# MC21R01_Onboard_temp_sensors.net
KiCad netlist of a schematic drawn in Altium Designer
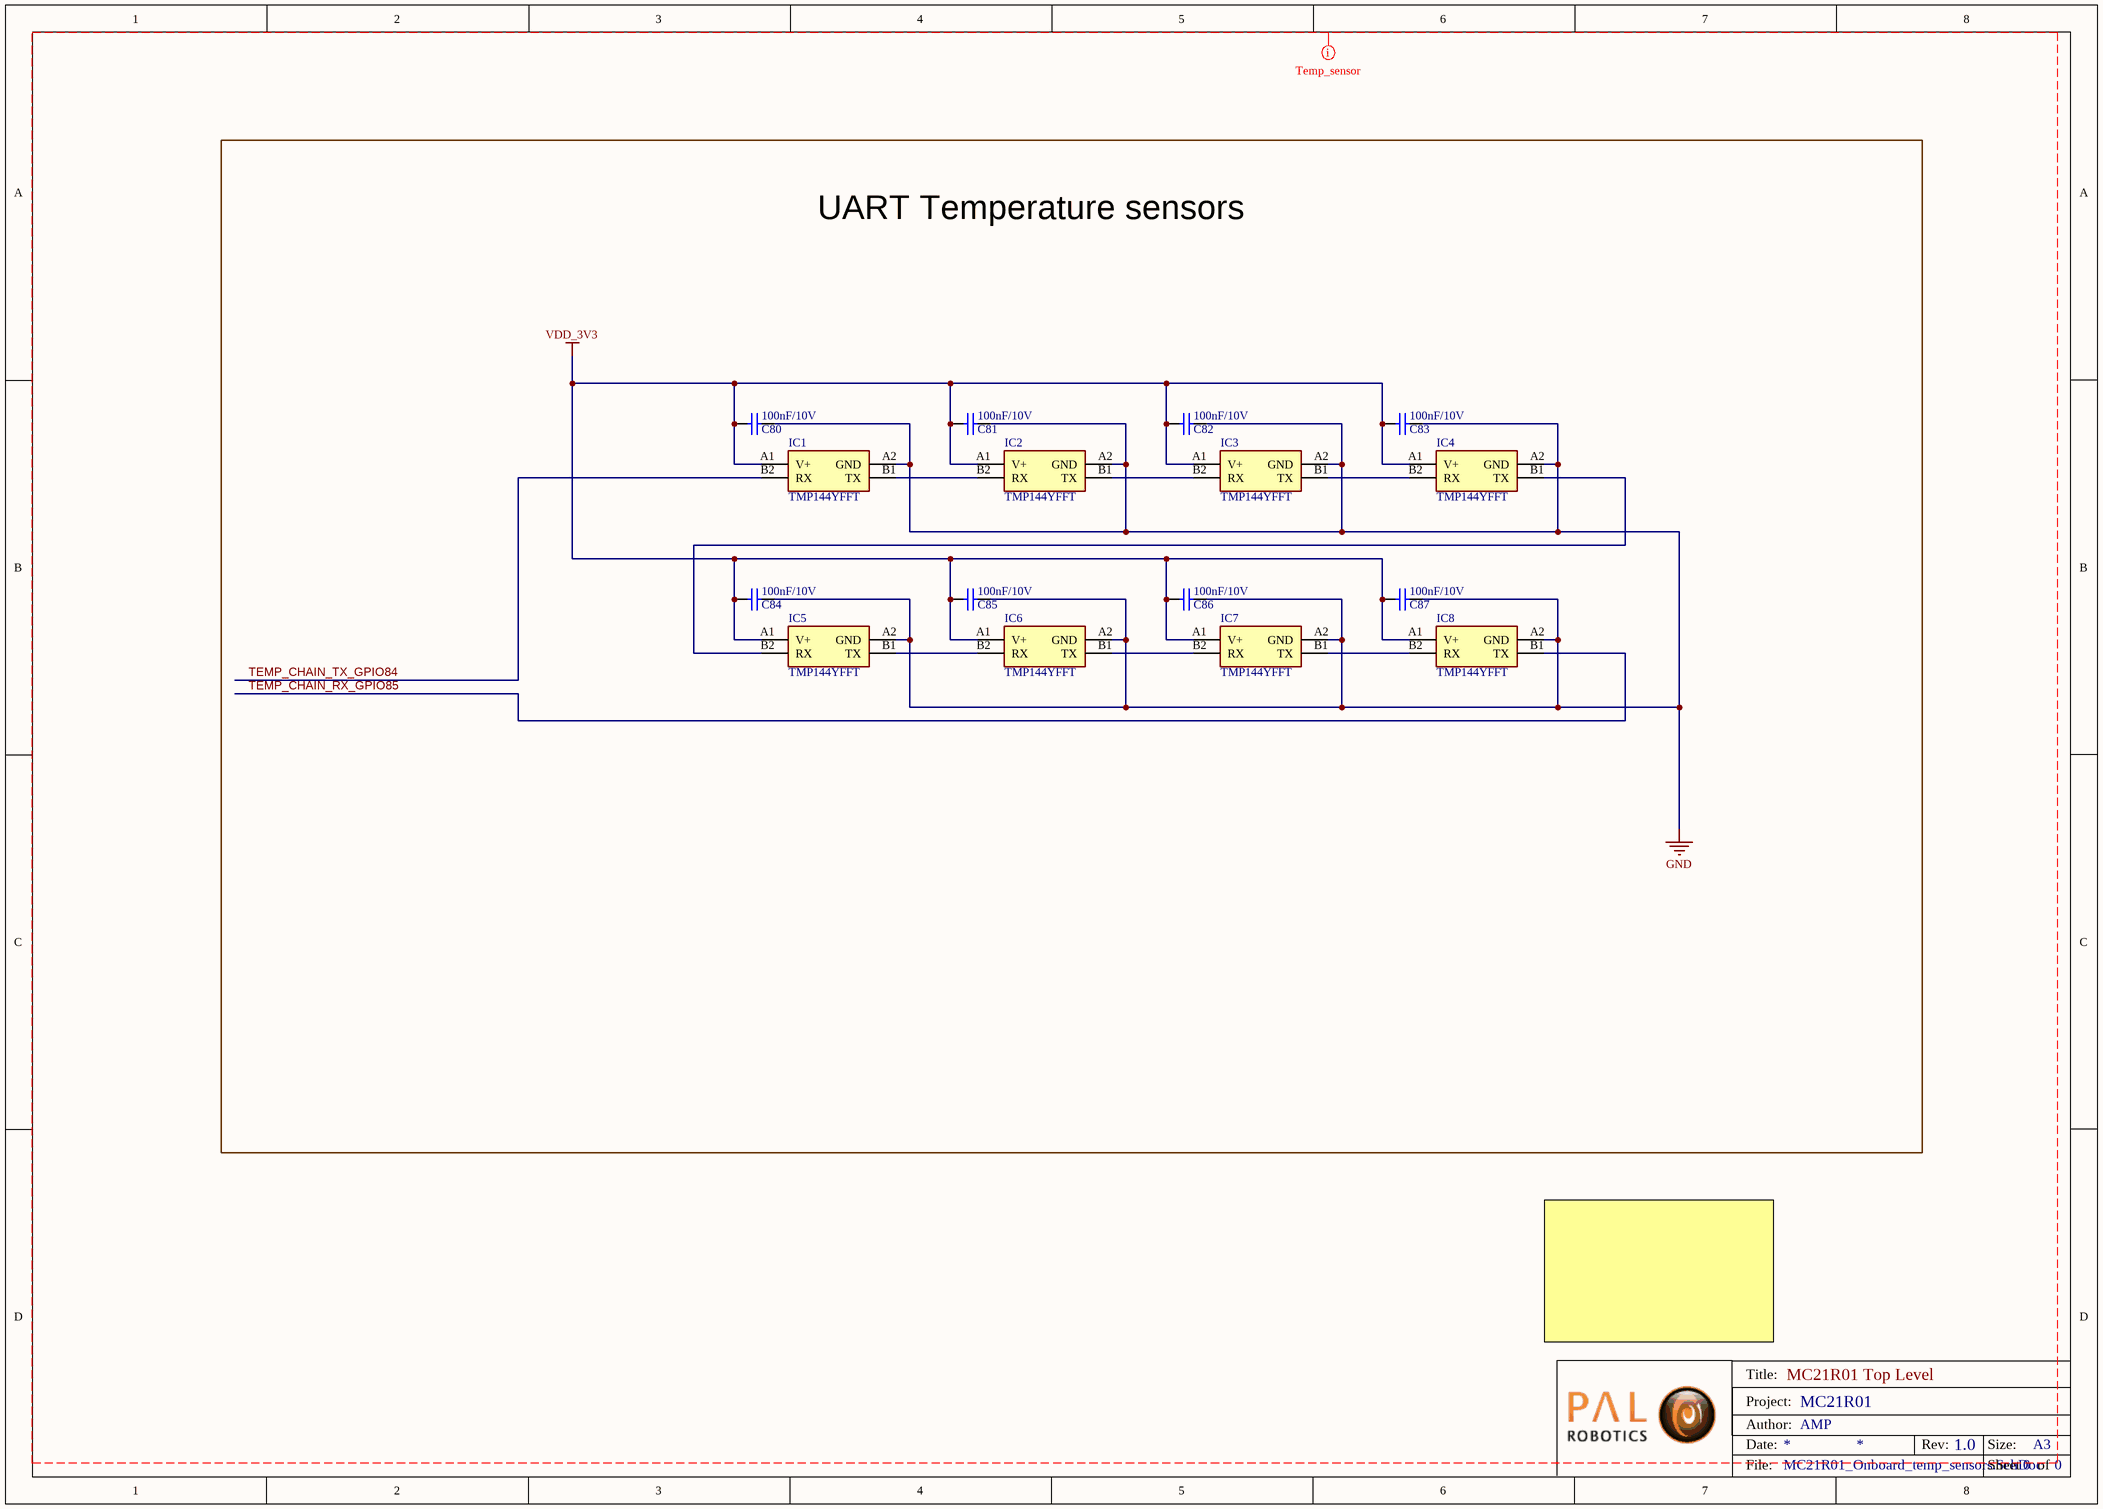
[diagram p0: MC21R01_Onboard_temp_sensors.SchDoc]

(export (version "E")
  (design (tool "Eeschema 10.0.6"))
  (components
    (comp (ref "C80")
      (value "100nF/10V")
      (footprint "PAL_Capacitors:0402 SMD Capacitor")
      (description "100nF/10V 0402 20% Tolerance X5R Multilayer Ceramic Chip Capacitor")
      (fields (field (name "Comment") "100nF/10V 0402 20% X5R"))
      (libsource (lib "PAL_Capacitors") (part "100nF/10V 0402 20% X5R"))
    )
    (comp (ref "C81")
      (value "100nF/10V")
      (footprint "PAL_Capacitors:0402 SMD Capacitor")
      (description "100nF/10V 0402 20% Tolerance X5R Multilayer Ceramic Chip Capacitor")
      (fields (field (name "Comment") "100nF/10V 0402 20% X5R"))
      (libsource (lib "PAL_Capacitors") (part "100nF/10V 0402 20% X5R"))
    )
    (comp (ref "C82")
      (value "100nF/10V")
      (footprint "PAL_Capacitors:0402 SMD Capacitor")
      (description "100nF/10V 0402 20% Tolerance X5R Multilayer Ceramic Chip Capacitor")
      (fields (field (name "Comment") "100nF/10V 0402 20% X5R"))
      (libsource (lib "PAL_Capacitors") (part "100nF/10V 0402 20% X5R"))
    )
    (comp (ref "C83")
      (value "100nF/10V")
      (footprint "PAL_Capacitors:0402 SMD Capacitor")
      (description "100nF/10V 0402 20% Tolerance X5R Multilayer Ceramic Chip Capacitor")
      (fields (field (name "Comment") "100nF/10V 0402 20% X5R"))
      (libsource (lib "PAL_Capacitors") (part "100nF/10V 0402 20% X5R"))
    )
    (comp (ref "C84")
      (value "100nF/10V")
      (footprint "PAL_Capacitors:0402 SMD Capacitor")
      (description "100nF/10V 0402 20% Tolerance X5R Multilayer Ceramic Chip Capacitor")
      (fields (field (name "Comment") "100nF/10V 0402 20% X5R"))
      (libsource (lib "PAL_Capacitors") (part "100nF/10V 0402 20% X5R"))
    )
    (comp (ref "C85")
      (value "100nF/10V")
      (footprint "PAL_Capacitors:0402 SMD Capacitor")
      (description "100nF/10V 0402 20% Tolerance X5R Multilayer Ceramic Chip Capacitor")
      (fields (field (name "Comment") "100nF/10V 0402 20% X5R"))
      (libsource (lib "PAL_Capacitors") (part "100nF/10V 0402 20% X5R"))
    )
    (comp (ref "C86")
      (value "100nF/10V")
      (footprint "PAL_Capacitors:0402 SMD Capacitor")
      (description "100nF/10V 0402 20% Tolerance X5R Multilayer Ceramic Chip Capacitor")
      (fields (field (name "Comment") "100nF/10V 0402 20% X5R"))
      (libsource (lib "PAL_Capacitors") (part "100nF/10V 0402 20% X5R"))
    )
    (comp (ref "C87")
      (value "100nF/10V")
      (footprint "PAL_Capacitors:0402 SMD Capacitor")
      (description "100nF/10V 0402 20% Tolerance X5R Multilayer Ceramic Chip Capacitor")
      (fields (field (name "Comment") "100nF/10V 0402 20% X5R"))
      (libsource (lib "PAL_Capacitors") (part "100nF/10V 0402 20% X5R"))
    )
    (comp (ref "IC1")
      (value "TMP144YFFT")
      (footprint "PAL_devices:TMP144YFFT")
      (description "Integrated Circuit")
      (fields (field (name "MOUSER PART NUMBER") "595-TMP144YFFT"))
      (libsource (lib "PAL_devices") (part "TMP144YFFT"))
    )
    (comp (ref "IC2")
      (value "TMP144YFFT")
      (footprint "PAL_devices:TMP144YFFT")
      (description "Integrated Circuit")
      (fields (field (name "MOUSER PART NUMBER") "595-TMP144YFFT"))
      (libsource (lib "PAL_devices") (part "TMP144YFFT"))
    )
    (comp (ref "IC3")
      (value "TMP144YFFT")
      (footprint "PAL_devices:TMP144YFFT")
      (description "Integrated Circuit")
      (fields (field (name "MOUSER PART NUMBER") "595-TMP144YFFT"))
      (libsource (lib "PAL_devices") (part "TMP144YFFT"))
    )
    (comp (ref "IC4")
      (value "TMP144YFFT")
      (footprint "PAL_devices:TMP144YFFT")
      (description "Integrated Circuit")
      (fields (field (name "MOUSER PART NUMBER") "595-TMP144YFFT"))
      (libsource (lib "PAL_devices") (part "TMP144YFFT"))
    )
    (comp (ref "IC5")
      (value "TMP144YFFT")
      (footprint "PAL_devices:TMP144YFFT")
      (description "Integrated Circuit")
      (fields (field (name "MOUSER PART NUMBER") "595-TMP144YFFT"))
      (libsource (lib "PAL_devices") (part "TMP144YFFT"))
    )
    (comp (ref "IC6")
      (value "TMP144YFFT")
      (footprint "PAL_devices:TMP144YFFT")
      (description "Integrated Circuit")
      (fields (field (name "MOUSER PART NUMBER") "595-TMP144YFFT"))
      (libsource (lib "PAL_devices") (part "TMP144YFFT"))
    )
    (comp (ref "IC7")
      (value "TMP144YFFT")
      (footprint "PAL_devices:TMP144YFFT")
      (description "Integrated Circuit")
      (fields (field (name "MOUSER PART NUMBER") "595-TMP144YFFT"))
      (libsource (lib "PAL_devices") (part "TMP144YFFT"))
    )
    (comp (ref "IC8")
      (value "TMP144YFFT")
      (footprint "PAL_devices:TMP144YFFT")
      (description "Integrated Circuit")
      (fields (field (name "MOUSER PART NUMBER") "595-TMP144YFFT"))
      (libsource (lib "PAL_devices") (part "TMP144YFFT"))
    )
  )
  (nets
    (net (code "1") (name "/TEMP_CHAIN_RX_GPIO85") (class "Default")
      (node (ref "IC8") (pin "B1") (pinfunction "TX_B1") (pintype "passive"))
    )
    (net (code "2") (name "/TEMP_CHAIN_TX_GPIO84") (class "Default")
      (node (ref "IC1") (pin "B2") (pinfunction "RX_B2") (pintype "passive"))
    )
    (net (code "3") (name "GND") (class "Default")
      (node (ref "C80") (pin "2") (pinfunction "2_2") (pintype "passive"))
      (node (ref "C81") (pin "2") (pinfunction "2_2") (pintype "passive"))
      (node (ref "C82") (pin "2") (pinfunction "2_2") (pintype "passive"))
      (node (ref "C83") (pin "2") (pinfunction "2_2") (pintype "passive"))
      (node (ref "C84") (pin "2") (pinfunction "2_2") (pintype "passive"))
      (node (ref "C85") (pin "2") (pinfunction "2_2") (pintype "passive"))
      (node (ref "C86") (pin "2") (pinfunction "2_2") (pintype "passive"))
      (node (ref "C87") (pin "2") (pinfunction "2_2") (pintype "passive"))
      (node (ref "IC1") (pin "A2") (pinfunction "GND_A2") (pintype "passive"))
      (node (ref "IC2") (pin "A2") (pinfunction "GND_A2") (pintype "passive"))
      (node (ref "IC3") (pin "A2") (pinfunction "GND_A2") (pintype "passive"))
      (node (ref "IC4") (pin "A2") (pinfunction "GND_A2") (pintype "passive"))
      (node (ref "IC5") (pin "A2") (pinfunction "GND_A2") (pintype "passive"))
      (node (ref "IC6") (pin "A2") (pinfunction "GND_A2") (pintype "passive"))
      (node (ref "IC7") (pin "A2") (pinfunction "GND_A2") (pintype "passive"))
      (node (ref "IC8") (pin "A2") (pinfunction "GND_A2") (pintype "passive"))
    )
    (net (code "4") (name "Net-(IC1-TX)") (class "Default")
      (node (ref "IC1") (pin "B1") (pinfunction "TX_B1") (pintype "passive"))
      (node (ref "IC2") (pin "B2") (pinfunction "RX_B2") (pintype "passive"))
    )
    (net (code "5") (name "Net-(IC2-TX)") (class "Default")
      (node (ref "IC2") (pin "B1") (pinfunction "TX_B1") (pintype "passive"))
      (node (ref "IC3") (pin "B2") (pinfunction "RX_B2") (pintype "passive"))
    )
    (net (code "6") (name "Net-(IC3-TX)") (class "Default")
      (node (ref "IC3") (pin "B1") (pinfunction "TX_B1") (pintype "passive"))
      (node (ref "IC4") (pin "B2") (pinfunction "RX_B2") (pintype "passive"))
    )
    (net (code "7") (name "Net-(IC4-TX)") (class "Default")
      (node (ref "IC4") (pin "B1") (pinfunction "TX_B1") (pintype "passive"))
      (node (ref "IC5") (pin "B2") (pinfunction "RX_B2") (pintype "passive"))
    )
    (net (code "8") (name "Net-(IC5-TX)") (class "Default")
      (node (ref "IC5") (pin "B1") (pinfunction "TX_B1") (pintype "passive"))
      (node (ref "IC6") (pin "B2") (pinfunction "RX_B2") (pintype "passive"))
    )
    (net (code "9") (name "Net-(IC6-TX)") (class "Default")
      (node (ref "IC6") (pin "B1") (pinfunction "TX_B1") (pintype "passive"))
      (node (ref "IC7") (pin "B2") (pinfunction "RX_B2") (pintype "passive"))
    )
    (net (code "10") (name "Net-(IC7-TX)") (class "Default")
      (node (ref "IC7") (pin "B1") (pinfunction "TX_B1") (pintype "passive"))
      (node (ref "IC8") (pin "B2") (pinfunction "RX_B2") (pintype "passive"))
    )
    (net (code "11") (name "VDD_3V3") (class "Default")
      (node (ref "C80") (pin "1") (pinfunction "1_1") (pintype "passive"))
      (node (ref "C81") (pin "1") (pinfunction "1_1") (pintype "passive"))
      (node (ref "C82") (pin "1") (pinfunction "1_1") (pintype "passive"))
      (node (ref "C83") (pin "1") (pinfunction "1_1") (pintype "passive"))
      (node (ref "C84") (pin "1") (pinfunction "1_1") (pintype "passive"))
      (node (ref "C85") (pin "1") (pinfunction "1_1") (pintype "passive"))
      (node (ref "C86") (pin "1") (pinfunction "1_1") (pintype "passive"))
      (node (ref "C87") (pin "1") (pinfunction "1_1") (pintype "passive"))
      (node (ref "IC1") (pin "A1") (pinfunction "V+_A1") (pintype "passive"))
      (node (ref "IC2") (pin "A1") (pinfunction "V+_A1") (pintype "passive"))
      (node (ref "IC3") (pin "A1") (pinfunction "V+_A1") (pintype "passive"))
      (node (ref "IC4") (pin "A1") (pinfunction "V+_A1") (pintype "passive"))
      (node (ref "IC5") (pin "A1") (pinfunction "V+_A1") (pintype "passive"))
      (node (ref "IC6") (pin "A1") (pinfunction "V+_A1") (pintype "passive"))
      (node (ref "IC7") (pin "A1") (pinfunction "V+_A1") (pintype "passive"))
      (node (ref "IC8") (pin "A1") (pinfunction "V+_A1") (pintype "passive"))
    )
  )
)
